# Power_supply_BA50DD0WHFPCT.net
KiCad netlist of a schematic drawn in Altium Designer
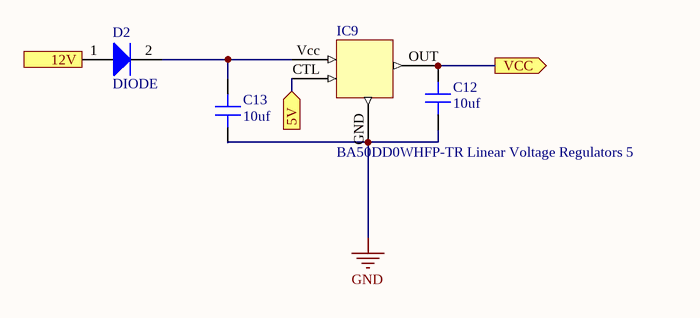
[diagram p0: Power_supply_BA50DD0WHFPCT.SchDoc]

(export (version "E")
  (design (tool "Eeschema 10.0.6"))
  (components
    (comp (ref "C12")
      (value "10uf")
      (footprint "CAP 0603/1608")
      (fields
        (field (name "Comment") "Capacitor MLCC 10uf 16V CAP 0603/1608")
        (field (name "CREATED_BY") "Nick Mah")
      )
      (libsource (lib "Altium-Lib") (part "Capacitor"))
    )
    (comp (ref "C13")
      (value "10uf")
      (footprint "CAP 0603/1608")
      (fields
        (field (name "Comment") "Capacitor MLCC 10uf 16V CAP 0603/1608")
        (field (name "CREATED_BY") "Nick Mah")
      )
      (libsource (lib "Altium-Lib") (part "Capacitor"))
    )
    (comp (ref "D2")
      (value "DIODE")
      (footprint "SODFL350X115-2M")
      (description "Diode Super Barrier 40V 1A Surface Mount SOD-123F")
      (fields (field (name "POWER") "40V") (field (name "MFRPARTNO") "1N5819HW1-7-F"))
      (libsource (lib "Altium-Lib") (part "DIODE"))
    )
    (comp (ref "IC9")
      (value "BA50DD0WHFP-TR Linear Voltage Regulators 5")
      (footprint "HRP5")
      (libsource (lib "Altium-Lib") (part "BA50DD0WHFP-TR Linear Voltage Regulators 5"))
    )
  )
  (nets
    (net (code "1") (name "/5V") (class "Default") (node (ref "IC9") (pin "CTL") (pintype "input")))
    (net (code "2") (name "/12V") (class "Default")
      (node (ref "D2") (pin "1") (pinfunction "A_1") (pintype "passive"))
    )
    (net (code "3") (name "/VCC") (class "Default")
      (node (ref "C12") (pin "2") (pinfunction "2_2") (pintype "passive"))
      (node (ref "IC9") (pin "OUT") (pintype "output"))
    )
    (net (code "4") (name "GND") (class "Default")
      (node (ref "C12") (pin "1") (pinfunction "1_1") (pintype "passive"))
      (node (ref "C13") (pin "1") (pinfunction "1_1") (pintype "passive"))
      (node (ref "IC9") (pin "GND") (pintype "output"))
    )
    (net (code "5") (name "Net-(D2-K)") (class "Default")
      (node (ref "C13") (pin "2") (pinfunction "2_2") (pintype "passive"))
      (node (ref "D2") (pin "2") (pinfunction "K_2") (pintype "passive"))
      (node (ref "IC9") (pin "Vcc") (pintype "input"))
    )
  )
)
